# v0_01.net
KiCad netlist of a schematic drawn in Altium Designer
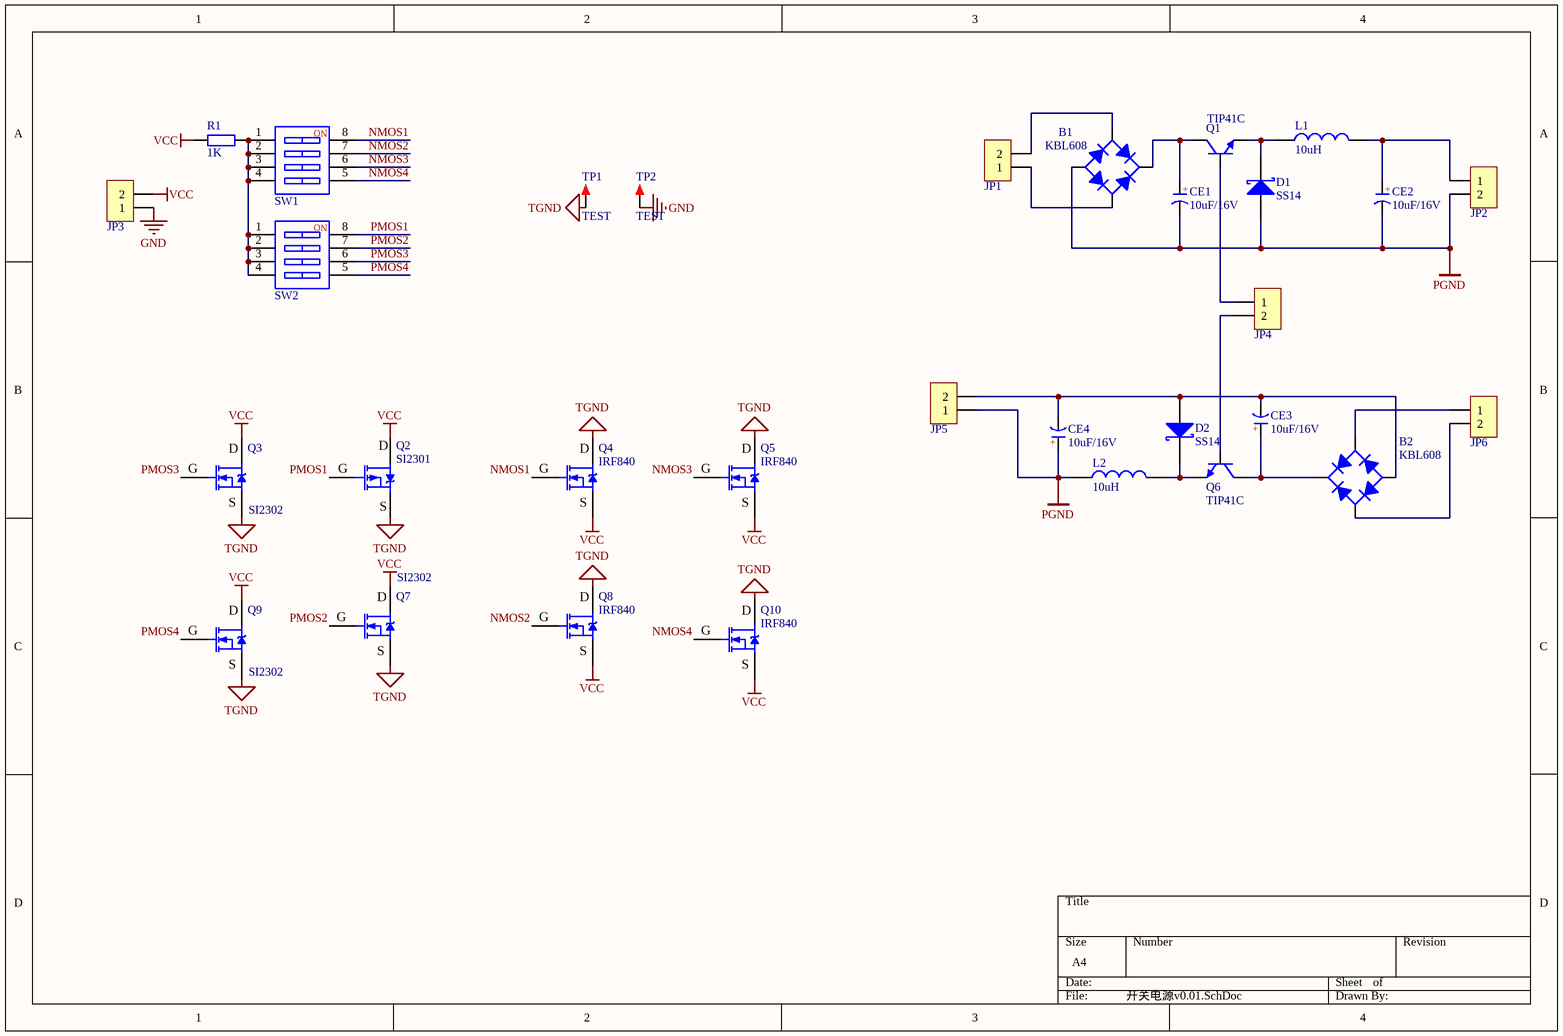
[diagram p0: 开关电源v0.01.SchDoc]

(export (version "E")
  (design (tool "Eeschema 10.0.6"))
  (components
    (comp (ref "B1")
      (value "KBL608")
      (footprint "KBP")
      (description "600V/8A整流桥")
      (fields (field (name "版权归属") "封装库来自淘宝卖家 ID：黄晶宝石"))
      (libsource (lib "0.2 -  二极管-整流桥") (part "KBL"))
    )
    (comp (ref "B2")
      (value "KBL608")
      (footprint "KBP")
      (description "600V/8A整流桥")
      (fields (field (name "版权归属") "封装库来自淘宝卖家 ID：黄晶宝石"))
      (libsource (lib "0.2 -  二极管-整流桥") (part "KBL"))
    )
    (comp (ref "CE1")
      (value "10uF/16V")
      (footprint "CAP 3.5*8*11.5 - BK")
      (description "直插电解电容")
      (libsource (lib "0.1 - 电阻-电容-电感") (part "CE"))
    )
    (comp (ref "CE2")
      (value "10uF/16V")
      (footprint "CAP 3.5*8*11.5 - BK")
      (description "直插电解电容")
      (libsource (lib "0.1 - 电阻-电容-电感") (part "CE"))
    )
    (comp (ref "CE3")
      (value "10uF/16V")
      (footprint "CAP 3.5*8*11.5 - BK")
      (description "直插电解电容")
      (libsource (lib "0.1 - 电阻-电容-电感") (part "CE"))
    )
    (comp (ref "CE4")
      (value "10uF/16V")
      (footprint "CAP 3.5*8*11.5 - BK")
      (description "直插电解电容")
      (libsource (lib "0.1 - 电阻-电容-电感") (part "CE"))
    )
    (comp (ref "D1")
      (value "SS14")
      (footprint "DO-201AD")
      (description "肖特基二极管")
      (libsource (lib "0.2 -  二极管-整流桥") (part "SS14"))
    )
    (comp (ref "D2")
      (value "SS14")
      (footprint "DO-201AD")
      (description "肖特基二极管")
      (libsource (lib "0.2 -  二极管-整流桥") (part "SS14"))
    )
    (comp (ref "JP1")
      (value "HDR-1X2")
      (footprint "KF7620-2P")
      (description "2P接插件")
      (fields (field (name "版权归属") "封装库来自淘宝 ID：黄晶宝石"))
      (libsource (lib "") (part "Header 2_1"))
    )
    (comp (ref "JP2")
      (value "HDR-1X2")
      (footprint "KF7620-2P")
      (description "2P接插件")
      (fields (field (name "版权归属") "封装库来自淘宝 ID：黄晶宝石"))
      (libsource (lib "5.3 - 接插件-脚距2.54 (100mil) ") (part "Header 2"))
    )
    (comp (ref "JP3")
      (value "HDR-1X2")
      (footprint "KF7620-2P")
      (description "2P接插件")
      (fields (field (name "版权归属") "封装库来自淘宝 ID：黄晶宝石"))
      (libsource (lib "") (part "Header 2_1"))
    )
    (comp (ref "JP4")
      (value "HDR-1X2")
      (footprint "HDR2.54-LI-2P")
      (description "2P接插件")
      (fields (field (name "版权归属") "封装库来自淘宝 ID：黄晶宝石"))
      (libsource (lib "5.3 - 接插件-脚距2.54 (100mil) ") (part "Header 2"))
    )
    (comp (ref "JP5")
      (value "HDR-1X2")
      (footprint "KF7620-2P")
      (description "2P接插件")
      (fields (field (name "版权归属") "封装库来自淘宝 ID：黄晶宝石"))
      (libsource (lib "") (part "Header 2_1"))
    )
    (comp (ref "JP6")
      (value "HDR-1X2")
      (footprint "KF7620-2P")
      (description "2P接插件")
      (fields (field (name "版权归属") "封装库来自淘宝 ID：黄晶宝石"))
      (libsource (lib "5.3 - 接插件-脚距2.54 (100mil) ") (part "Header 2"))
    )
    (comp (ref "L1")
      (value "10uH")
      (footprint "AL0410_V")
      (description "小功率贴片电感")
      (libsource (lib "0.1 - 电阻-电容-电感") (part "L"))
    )
    (comp (ref "L2")
      (value "10uH")
      (footprint "AL0410_V")
      (description "小功率贴片电感")
      (libsource (lib "0.1 - 电阻-电容-电感") (part "L"))
    )
    (comp (ref "Q1")
      (value "TIP41C")
      (footprint "TO220A")
      (description "互补功率-NPN型")
      (libsource (lib "0.4 - 三极管") (part "TIP41C"))
    )
    (comp (ref "Q2")
      (value "SI2301")
      (footprint "SOT23-3M")
      (description "P沟道场效应管")
      (libsource (lib "0.5 - 场效应管-可控硅") (part "SI2301"))
    )
    (comp (ref "Q3")
      (value "SI2302")
      (footprint "TO220A")
      (description "N沟道场效应管")
      (libsource (lib "0.5 - 场效应管-可控硅") (part "SI2302"))
    )
    (comp (ref "Q4")
      (value "IRF840")
      (footprint "SOT23-3M")
      (description "N沟场效应管")
      (libsource (lib "0.5 - 场效应管-可控硅") (part "IRF840"))
    )
    (comp (ref "Q5")
      (value "IRF840")
      (footprint "TO220A")
      (description "N沟场效应管")
      (libsource (lib "0.5 - 场效应管-可控硅") (part "IRF840"))
    )
    (comp (ref "Q6")
      (value "TIP41C")
      (footprint "TO220A")
      (description "互补功率-NPN型")
      (libsource (lib "0.4 - 三极管") (part "TIP41C"))
    )
    (comp (ref "Q7")
      (value "SI2302")
      (footprint "SOT23-3M")
      (description "N沟道场效应管")
      (libsource (lib "0.5 - 场效应管-可控硅") (part "SI2302"))
    )
    (comp (ref "Q8")
      (value "IRF840")
      (footprint "SOT23-3M")
      (description "N沟场效应管")
      (libsource (lib "0.5 - 场效应管-可控硅") (part "IRF840"))
    )
    (comp (ref "Q9")
      (value "SI2302")
      (footprint "TO220A")
      (description "N沟道场效应管")
      (libsource (lib "0.5 - 场效应管-可控硅") (part "SI2302"))
    )
    (comp (ref "Q10")
      (value "IRF840")
      (footprint "TO220A")
      (description "N沟场效应管")
      (libsource (lib "0.5 - 场效应管-可控硅") (part "IRF840"))
    )
    (comp (ref "R1")
      (value "1K")
      (footprint "RS 1/2W")
      (description "色环电阻")
      (fields (field (name "版权归属") "封装库来自淘宝 ID：黄晶宝石"))
      (libsource (lib "0.1 - 电阻-电容-电感") (part "R-S"))
    )
    (comp (ref "SW1")
      (value "SW-4P")
      (footprint "CSW DIP-4P")
      (description "4路编码开关")
      (libsource (lib "0.7 - 常用按键-开关") (part "SW-4P"))
    )
    (comp (ref "SW2")
      (value "SW-4P")
      (footprint "CSW DIP-4P")
      (description "4路编码开关")
      (libsource (lib "0.7 - 常用按键-开关") (part "SW-4P"))
    )
    (comp (ref "TP1")
      (value "TEST")
      (footprint "TEST 1")
      (description "测试点")
      (fields (field (name "版权归属") "封装库来自淘宝 ID：黄晶宝石"))
      (libsource (lib "4.1 - 未分类器件") (part "TEST"))
    )
    (comp (ref "TP2")
      (value "TEST")
      (footprint "TEST 1")
      (description "测试点")
      (fields (field (name "版权归属") "封装库来自淘宝 ID：黄晶宝石"))
      (libsource (lib "4.1 - 未分类器件") (part "TEST"))
    )
  )
  (nets
    (net (code "1") (name "/NMOS1") (class "Default")
      (node (ref "Q4") (pin "1") (pinfunction "G_1") (pintype "passive"))
      (node (ref "SW1") (pin "8") (pinfunction "8_8") (pintype "passive"))
    )
    (net (code "2") (name "/NMOS2") (class "Default")
      (node (ref "Q8") (pin "1") (pinfunction "G_1") (pintype "passive"))
      (node (ref "SW1") (pin "7") (pinfunction "7_7") (pintype "passive"))
    )
    (net (code "3") (name "/NMOS3") (class "Default")
      (node (ref "Q5") (pin "1") (pinfunction "G_1") (pintype "passive"))
      (node (ref "SW1") (pin "6") (pinfunction "6_6") (pintype "passive"))
    )
    (net (code "4") (name "/NMOS4") (class "Default")
      (node (ref "Q10") (pin "1") (pinfunction "G_1") (pintype "passive"))
      (node (ref "SW1") (pin "5") (pinfunction "5_5") (pintype "passive"))
    )
    (net (code "5") (name "/PMOS1") (class "Default")
      (node (ref "Q2") (pin "1") (pinfunction "G_1") (pintype "passive"))
      (node (ref "SW2") (pin "8") (pinfunction "8_8") (pintype "passive"))
    )
    (net (code "6") (name "/PMOS2") (class "Default")
      (node (ref "Q7") (pin "1") (pinfunction "G_1") (pintype "passive"))
      (node (ref "SW2") (pin "7") (pinfunction "7_7") (pintype "passive"))
    )
    (net (code "7") (name "/PMOS3") (class "Default")
      (node (ref "Q3") (pin "1") (pinfunction "G_1") (pintype "passive"))
      (node (ref "SW2") (pin "6") (pinfunction "6_6") (pintype "passive"))
    )
    (net (code "8") (name "/PMOS4") (class "Default")
      (node (ref "Q9") (pin "1") (pinfunction "G_1") (pintype "passive"))
      (node (ref "SW2") (pin "5") (pinfunction "5_5") (pintype "passive"))
    )
    (net (code "9") (name "GND") (class "Default")
      (node (ref "JP3") (pin "1") (pinfunction "1_1") (pintype "passive"))
      (node (ref "TP2") (pin "1") (pinfunction "1_1") (pintype "passive"))
    )
    (net (code "10") (name "Net-(B1-PadAC1)") (class "Default")
      (node (ref "B1") (pin "AC1") (pinfunction "AC1_AC1") (pintype "passive"))
      (node (ref "JP1") (pin "2") (pinfunction "2_2") (pintype "passive"))
    )
    (net (code "11") (name "Net-(B1-PadAC2)") (class "Default")
      (node (ref "B1") (pin "AC2") (pinfunction "AC2_AC2") (pintype "passive"))
      (node (ref "JP1") (pin "1") (pinfunction "1_1") (pintype "passive"))
    )
    (net (code "12") (name "Net-(B2-PadAC1)") (class "Default")
      (node (ref "B2") (pin "AC1") (pinfunction "AC1_AC1") (pintype "passive"))
      (node (ref "JP6") (pin "2") (pinfunction "2_2") (pintype "passive"))
    )
    (net (code "13") (name "Net-(B2-PadAC2)") (class "Default")
      (node (ref "B2") (pin "AC2") (pinfunction "AC2_AC2") (pintype "passive"))
      (node (ref "JP6") (pin "1") (pinfunction "1_1") (pintype "passive"))
    )
    (net (code "14") (name "Net-(CE1-A)") (class "Default")
      (node (ref "B1") (pin "DC+") (pinfunction "DC+_DC+") (pintype "passive"))
      (node (ref "CE1") (pin "1") (pinfunction "A_1") (pintype "passive"))
      (node (ref "Q1") (pin "2") (pinfunction "C_2") (pintype "passive"))
    )
    (net (code "15") (name "Net-(CE2-A)") (class "Default")
      (node (ref "CE2") (pin "1") (pinfunction "A_1") (pintype "passive"))
      (node (ref "JP2") (pin "1") (pinfunction "1_1") (pintype "passive"))
      (node (ref "L1") (pin "2") (pinfunction "2_2") (pintype "passive"))
    )
    (net (code "16") (name "Net-(CE3-A)") (class "Default")
      (node (ref "B2") (pin "DC+") (pinfunction "DC+_DC+") (pintype "passive"))
      (node (ref "CE3") (pin "1") (pinfunction "A_1") (pintype "passive"))
      (node (ref "Q6") (pin "2") (pinfunction "C_2") (pintype "passive"))
    )
    (net (code "17") (name "Net-(CE3-K)") (class "Default")
      (node (ref "B2") (pin "DC-") (pinfunction "DC-_DC-") (pintype "passive"))
      (node (ref "CE3") (pin "2") (pinfunction "K_2") (pintype "passive"))
      (node (ref "CE4") (pin "2") (pinfunction "K_2") (pintype "passive"))
      (node (ref "D2") (pin "1") (pinfunction "A_1") (pintype "passive"))
      (node (ref "JP5") (pin "2") (pinfunction "2_2") (pintype "passive"))
    )
    (net (code "18") (name "Net-(D1-K)") (class "Default")
      (node (ref "D1") (pin "2") (pinfunction "K_2") (pintype "passive"))
      (node (ref "L1") (pin "1") (pinfunction "1_1") (pintype "passive"))
      (node (ref "Q1") (pin "3") (pinfunction "E_3") (pintype "passive"))
    )
    (net (code "19") (name "Net-(D2-K)") (class "Default")
      (node (ref "D2") (pin "2") (pinfunction "K_2") (pintype "passive"))
      (node (ref "L2") (pin "2") (pinfunction "2_2") (pintype "passive"))
      (node (ref "Q6") (pin "3") (pinfunction "E_3") (pintype "passive"))
    )
    (net (code "20") (name "Net-(Q1-B)") (class "Default")
      (node (ref "JP4") (pin "1") (pinfunction "1_1") (pintype "passive"))
      (node (ref "Q1") (pin "1") (pinfunction "B_1") (pintype "passive"))
    )
    (net (code "21") (name "Net-(Q6-B)") (class "Default")
      (node (ref "JP4") (pin "2") (pinfunction "2_2") (pintype "passive"))
      (node (ref "Q6") (pin "1") (pinfunction "B_1") (pintype "passive"))
    )
    (net (code "22") (name "Net-(R1-Pad2)") (class "Default")
      (node (ref "R1") (pin "2") (pinfunction "2_2") (pintype "passive"))
      (node (ref "SW1") (pin "1") (pinfunction "1_1") (pintype "passive"))
      (node (ref "SW1") (pin "2") (pinfunction "2_2") (pintype "passive"))
      (node (ref "SW1") (pin "3") (pinfunction "3_3") (pintype "passive"))
      (node (ref "SW1") (pin "4") (pinfunction "4_4") (pintype "passive"))
      (node (ref "SW2") (pin "1") (pinfunction "1_1") (pintype "passive"))
      (node (ref "SW2") (pin "2") (pinfunction "2_2") (pintype "passive"))
      (node (ref "SW2") (pin "3") (pinfunction "3_3") (pintype "passive"))
      (node (ref "SW2") (pin "4") (pinfunction "4_4") (pintype "passive"))
    )
    (net (code "23") (name "PGND") (class "Default")
      (node (ref "B1") (pin "DC-") (pinfunction "DC-_DC-") (pintype "passive"))
      (node (ref "CE1") (pin "2") (pinfunction "K_2") (pintype "passive"))
      (node (ref "CE2") (pin "2") (pinfunction "K_2") (pintype "passive"))
      (node (ref "CE4") (pin "1") (pinfunction "A_1") (pintype "passive"))
      (node (ref "D1") (pin "1") (pinfunction "A_1") (pintype "passive"))
      (node (ref "JP2") (pin "2") (pinfunction "2_2") (pintype "passive"))
      (node (ref "JP5") (pin "1") (pinfunction "1_1") (pintype "passive"))
      (node (ref "L2") (pin "1") (pinfunction "1_1") (pintype "passive"))
    )
    (net (code "24") (name "TGND") (class "Default")
      (node (ref "Q10") (pin "2") (pinfunction "D_2") (pintype "passive"))
      (node (ref "Q2") (pin "2") (pinfunction "S_2") (pintype "passive"))
      (node (ref "Q3") (pin "2") (pinfunction "S_2") (pintype "passive"))
      (node (ref "Q4") (pin "2") (pinfunction "D_2") (pintype "passive"))
      (node (ref "Q5") (pin "2") (pinfunction "D_2") (pintype "passive"))
      (node (ref "Q7") (pin "2") (pinfunction "S_2") (pintype "passive"))
      (node (ref "Q8") (pin "2") (pinfunction "D_2") (pintype "passive"))
      (node (ref "Q9") (pin "2") (pinfunction "S_2") (pintype "passive"))
      (node (ref "TP1") (pin "1") (pinfunction "1_1") (pintype "passive"))
    )
    (net (code "25") (name "VCC") (class "Default")
      (node (ref "JP3") (pin "2") (pinfunction "2_2") (pintype "passive"))
      (node (ref "Q10") (pin "3") (pinfunction "S_3") (pintype "passive"))
      (node (ref "Q2") (pin "3") (pinfunction "D_3") (pintype "passive"))
      (node (ref "Q3") (pin "3") (pinfunction "D_3") (pintype "passive"))
      (node (ref "Q4") (pin "3") (pinfunction "S_3") (pintype "passive"))
      (node (ref "Q5") (pin "3") (pinfunction "S_3") (pintype "passive"))
      (node (ref "Q7") (pin "3") (pinfunction "D_3") (pintype "passive"))
      (node (ref "Q8") (pin "3") (pinfunction "S_3") (pintype "passive"))
      (node (ref "Q9") (pin "3") (pinfunction "D_3") (pintype "passive"))
      (node (ref "R1") (pin "1") (pinfunction "1_1") (pintype "passive"))
    )
  )
)
